# TH8_EEM_connector.net
KiCad netlist of a schematic drawn in Altium Designer
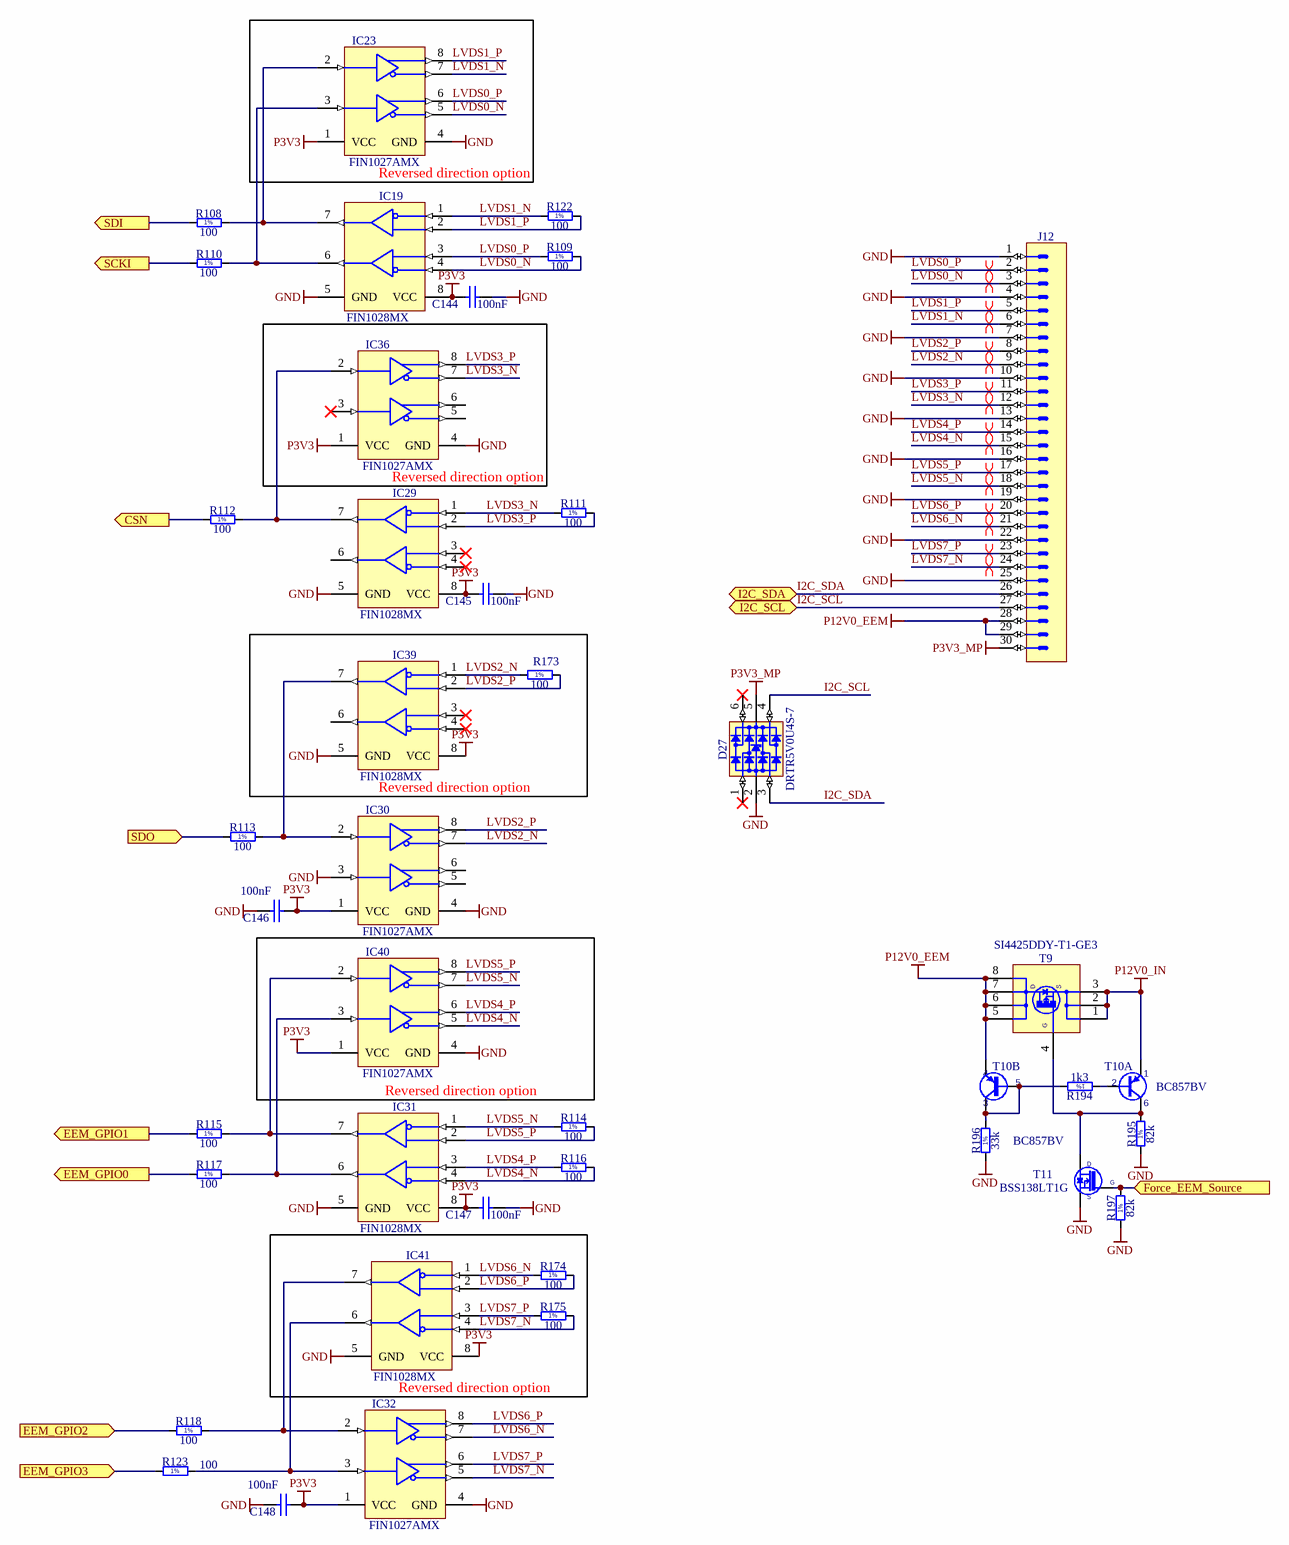
[diagram p0: TH8_EEM_connector.SchDoc]

(export (version "E")
  (design (tool "Eeschema 10.0.6"))
  (components
    (comp (ref "C144")
      (value "100nF")
      (footprint "CAPC1005X55N")
      (description "Non-polarised capacitor")
      (fields
        (field (name "PART NUMBER") "CC0402_100NF_16V_10%_X5R")
        (field (name "VOLTAGE") "16V")
        (field (name "AUTHOR") "CERN DEM JLC")
      )
      (libsource (lib "Capacitors") (part "Capacitor - non polarized"))
    )
    (comp (ref "C145")
      (value "100nF")
      (footprint "CAPC1005X55N")
      (description "Non-polarised capacitor")
      (fields
        (field (name "PART NUMBER") "CC0402_100NF_16V_10%_X5R")
        (field (name "VOLTAGE") "16V")
        (field (name "AUTHOR") "CERN DEM JLC")
      )
      (libsource (lib "Capacitors") (part "Capacitor - non polarized"))
    )
    (comp (ref "C146")
      (value "100nF")
      (footprint "CAPC1005X55N")
      (description "Non-polarised capacitor")
      (fields
        (field (name "PART NUMBER") "CC0402_100NF_16V_10%_X5R")
        (field (name "VOLTAGE") "16V")
        (field (name "AUTHOR") "CERN DEM JLC")
      )
      (libsource (lib "Capacitors") (part "Capacitor - non polarized"))
    )
    (comp (ref "C147")
      (value "100nF")
      (footprint "CAPC1005X55N")
      (description "Non-polarised capacitor")
      (fields
        (field (name "PART NUMBER") "CC0402_100NF_16V_10%_X5R")
        (field (name "VOLTAGE") "16V")
        (field (name "AUTHOR") "CERN DEM JLC")
      )
      (libsource (lib "Capacitors") (part "Capacitor - non polarized"))
    )
    (comp (ref "C148")
      (value "100nF")
      (footprint "CAPC1005X55N")
      (description "Non-polarised capacitor")
      (fields
        (field (name "PART NUMBER") "CC0402_100NF_16V_10%_X5R")
        (field (name "VOLTAGE") "16V")
        (field (name "AUTHOR") "CERN DEM JLC")
      )
      (libsource (lib "Capacitors") (part "Capacitor - non polarized"))
    )
    (comp (ref "D27")
      (value "DRTR5V0U4S-7")
      (footprint "SOT65P210X110-6N")
      (description "Integrated Quad Ultra-Low Capacitance ESD Protection")
      (fields (field (name "MANUFACTURER") "DIODES") (field (name "AUTHOR") "GK"))
      (libsource (lib "Diodes") (part "D_TVS_DRTR5V0U4S-7"))
    )
    (comp (ref "IC19")
      (value "FIN1028MX")
      (footprint "SOIC127P600X175-8N")
      (description "3.3V LVDS 2-Bit High-Speed Differential Reciever")
      (fields (field (name "MANUFACTURER") "ON Semiconductor") (field (name "AUTHOR") "GK"))
      (libsource (lib "LIBRARY_SCH") (part "IFC_FIN1028"))
    )
    (comp (ref "IC23")
      (value "FIN1027AMX")
      (footprint "SOIC127P600X175-8N")
      (description "3.3V LVDS, 2-Bit, High-Speed, Differential Driver")
      (fields (field (name "MANUFACTURER") "ON Semiconductor") (field (name "AUTHOR") "GK"))
      (libsource (lib "LIBRARY_SCH") (part "IFC_FIN1027A"))
    )
    (comp (ref "IC29")
      (value "FIN1028MX")
      (footprint "SOIC127P600X175-8N")
      (description "3.3V LVDS 2-Bit High-Speed Differential Reciever")
      (fields (field (name "MANUFACTURER") "ON Semiconductor") (field (name "AUTHOR") "GK"))
      (libsource (lib "LIBRARY_SCH") (part "IFC_FIN1028"))
    )
    (comp (ref "IC30")
      (value "FIN1027AMX")
      (footprint "SOIC127P600X175-8N")
      (description "3.3V LVDS, 2-Bit, High-Speed, Differential Driver")
      (fields (field (name "MANUFACTURER") "ON Semiconductor") (field (name "AUTHOR") "GK"))
      (libsource (lib "LIBRARY_SCH") (part "IFC_FIN1027A"))
    )
    (comp (ref "IC31")
      (value "FIN1028MX")
      (footprint "SOIC127P600X175-8N")
      (description "3.3V LVDS 2-Bit High-Speed Differential Reciever")
      (fields (field (name "MANUFACTURER") "ON Semiconductor") (field (name "AUTHOR") "GK"))
      (libsource (lib "LIBRARY_SCH") (part "IFC_FIN1028"))
    )
    (comp (ref "IC32")
      (value "FIN1027AMX")
      (footprint "SOIC127P600X175-8N")
      (description "3.3V LVDS, 2-Bit, High-Speed, Differential Driver")
      (fields (field (name "MANUFACTURER") "ON Semiconductor") (field (name "AUTHOR") "GK"))
      (libsource (lib "LIBRARY_SCH") (part "IFC_FIN1027A"))
    )
    (comp (ref "IC36")
      (value "FIN1027AMX")
      (footprint "SOIC127P600X175-8N")
      (description "3.3V LVDS, 2-Bit, High-Speed, Differential Driver")
      (fields (field (name "MANUFACTURER") "ON Semiconductor") (field (name "AUTHOR") "GK"))
      (libsource (lib "LIBRARY_SCH") (part "IFC_FIN1027A"))
    )
    (comp (ref "IC39")
      (value "FIN1028MX")
      (footprint "SOIC127P600X175-8N")
      (description "3.3V LVDS 2-Bit High-Speed Differential Reciever")
      (fields (field (name "MANUFACTURER") "ON Semiconductor") (field (name "AUTHOR") "GK"))
      (libsource (lib "LIBRARY_SCH") (part "IFC_FIN1028"))
    )
    (comp (ref "IC40")
      (value "FIN1027AMX")
      (footprint "SOIC127P600X175-8N")
      (description "3.3V LVDS, 2-Bit, High-Speed, Differential Driver")
      (fields (field (name "MANUFACTURER") "ON Semiconductor") (field (name "AUTHOR") "GK"))
      (libsource (lib "LIBRARY_SCH") (part "IFC_FIN1027A"))
    )
    (comp (ref "IC41")
      (value "FIN1028MX")
      (footprint "SOIC127P600X175-8N")
      (description "3.3V LVDS 2-Bit High-Speed Differential Reciever")
      (fields (field (name "MANUFACTURER") "ON Semiconductor") (field (name "AUTHOR") "GK"))
      (libsource (lib "LIBRARY_SCH") (part "IFC_FIN1028"))
    )
    (comp (ref "J12")
      (value "~")
      (footprint "3M_N2530-6002RB")
      (description "Connector 30 Male")
      (fields
        (field (name "PART NUMBER") "3M_N2530-6002RB")
        (field (name "MANUFACTURER") "3M")
        (field (name "AUTHOR") "CERN DEM JLC")
      )
      (libsource (lib "Connectors") (part "Connector 30 Male"))
    )
    (comp (ref "R108")
      (value "100")
      (footprint "RESC1005X40N")
      (description "Resistor - 1%")
      (fields
        (field (name "PART NUMBER") "R0402_100R_1%_0.0625W_100PPM")
        (field (name "POWER") "0.0625W")
        (field (name "AUTHOR") "CERN DEM JLC")
      )
      (libsource (lib "Resistors") (part "Resistor - 1%"))
    )
    (comp (ref "R109")
      (value "100")
      (footprint "RESC1005X40N")
      (description "Resistor - 1%")
      (fields
        (field (name "PART NUMBER") "R0402_100R_1%_0.0625W_100PPM")
        (field (name "POWER") "0.0625W")
        (field (name "AUTHOR") "CERN DEM JLC")
      )
      (libsource (lib "Resistors") (part "Resistor - 1%"))
    )
    (comp (ref "R110")
      (value "100")
      (footprint "RESC1005X40N")
      (description "Resistor - 1%")
      (fields
        (field (name "PART NUMBER") "R0402_100R_1%_0.0625W_100PPM")
        (field (name "POWER") "0.0625W")
        (field (name "AUTHOR") "CERN DEM JLC")
      )
      (libsource (lib "Resistors") (part "Resistor - 1%"))
    )
    (comp (ref "R111")
      (value "100")
      (footprint "RESC1005X40N")
      (description "Resistor - 1%")
      (fields
        (field (name "PART NUMBER") "R0402_100R_1%_0.0625W_100PPM")
        (field (name "POWER") "0.0625W")
        (field (name "AUTHOR") "CERN DEM JLC")
      )
      (libsource (lib "Resistors") (part "Resistor - 1%"))
    )
    (comp (ref "R112")
      (value "100")
      (footprint "RESC1005X40N")
      (description "Resistor - 1%")
      (fields
        (field (name "PART NUMBER") "R0402_100R_1%_0.0625W_100PPM")
        (field (name "POWER") "0.0625W")
        (field (name "AUTHOR") "CERN DEM JLC")
      )
      (libsource (lib "Resistors") (part "Resistor - 1%"))
    )
    (comp (ref "R113")
      (value "100")
      (footprint "RESC1005X40N")
      (description "Resistor - 1%")
      (fields
        (field (name "PART NUMBER") "R0402_100R_1%_0.0625W_100PPM")
        (field (name "POWER") "0.0625W")
        (field (name "AUTHOR") "CERN DEM JLC")
      )
      (libsource (lib "Resistors") (part "Resistor - 1%"))
    )
    (comp (ref "R114")
      (value "100")
      (footprint "RESC1005X40N")
      (description "Resistor - 1%")
      (fields
        (field (name "PART NUMBER") "R0402_100R_1%_0.0625W_100PPM")
        (field (name "POWER") "0.0625W")
        (field (name "AUTHOR") "CERN DEM JLC")
      )
      (libsource (lib "Resistors") (part "Resistor - 1%"))
    )
    (comp (ref "R115")
      (value "100")
      (footprint "RESC1005X40N")
      (description "Resistor - 1%")
      (fields
        (field (name "PART NUMBER") "R0402_100R_1%_0.0625W_100PPM")
        (field (name "POWER") "0.0625W")
        (field (name "AUTHOR") "CERN DEM JLC")
      )
      (libsource (lib "Resistors") (part "Resistor - 1%"))
    )
    (comp (ref "R116")
      (value "100")
      (footprint "RESC1005X40N")
      (description "Resistor - 1%")
      (fields
        (field (name "PART NUMBER") "R0402_100R_1%_0.0625W_100PPM")
        (field (name "POWER") "0.0625W")
        (field (name "AUTHOR") "CERN DEM JLC")
      )
      (libsource (lib "Resistors") (part "Resistor - 1%"))
    )
    (comp (ref "R117")
      (value "100")
      (footprint "RESC1005X40N")
      (description "Resistor - 1%")
      (fields
        (field (name "PART NUMBER") "R0402_100R_1%_0.0625W_100PPM")
        (field (name "POWER") "0.0625W")
        (field (name "AUTHOR") "CERN DEM JLC")
      )
      (libsource (lib "Resistors") (part "Resistor - 1%"))
    )
    (comp (ref "R118")
      (value "100")
      (footprint "RESC1005X40N")
      (description "Resistor - 1%")
      (fields
        (field (name "PART NUMBER") "R0402_100R_1%_0.0625W_100PPM")
        (field (name "POWER") "0.0625W")
        (field (name "AUTHOR") "CERN DEM JLC")
      )
      (libsource (lib "Resistors") (part "Resistor - 1%"))
    )
    (comp (ref "R122")
      (value "100")
      (footprint "RESC1005X40N")
      (description "Resistor - 1%")
      (fields
        (field (name "PART NUMBER") "R0402_100R_1%_0.0625W_100PPM")
        (field (name "POWER") "0.0625W")
        (field (name "AUTHOR") "CERN DEM JLC")
      )
      (libsource (lib "Resistors") (part "Resistor - 1%"))
    )
    (comp (ref "R123")
      (value "100")
      (footprint "RESC1005X40N")
      (description "Resistor - 1%")
      (fields
        (field (name "PART NUMBER") "R0402_100R_1%_0.0625W_100PPM")
        (field (name "POWER") "0.0625W")
        (field (name "AUTHOR") "CERN DEM JLC")
      )
      (libsource (lib "Resistors") (part "Resistor - 1%"))
    )
    (comp (ref "R173")
      (value "100")
      (footprint "RESC1005X40N")
      (description "Resistor - 1%")
      (fields
        (field (name "PART NUMBER") "R0402_100R_1%_0.0625W_100PPM")
        (field (name "POWER") "0.0625W")
        (field (name "AUTHOR") "CERN DEM JLC")
      )
      (libsource (lib "Resistors") (part "Resistor - 1%"))
    )
    (comp (ref "R174")
      (value "100")
      (footprint "RESC1005X40N")
      (description "Resistor - 1%")
      (fields
        (field (name "PART NUMBER") "R0402_100R_1%_0.0625W_100PPM")
        (field (name "POWER") "0.0625W")
        (field (name "AUTHOR") "CERN DEM JLC")
      )
      (libsource (lib "Resistors") (part "Resistor - 1%"))
    )
    (comp (ref "R175")
      (value "100")
      (footprint "RESC1005X40N")
      (description "Resistor - 1%")
      (fields
        (field (name "PART NUMBER") "R0402_100R_1%_0.0625W_100PPM")
        (field (name "POWER") "0.0625W")
        (field (name "AUTHOR") "CERN DEM JLC")
      )
      (libsource (lib "Resistors") (part "Resistor - 1%"))
    )
    (comp (ref "R194")
      (value "1k3")
      (footprint "RESC1608X55N")
      (description "Resistor - 1%")
      (fields
        (field (name "PART NUMBER") "R0603_1K3_1%_0.1W_100PPM")
        (field (name "POWER") "0.1W")
        (field (name "AUTHOR") "CERN DEM JLC")
      )
      (libsource (lib "Resistors") (part "Resistor - 1%"))
    )
    (comp (ref "R195")
      (value "82k")
      (footprint "RESC1608X55N")
      (description "Resistor - 1%")
      (fields
        (field (name "PART NUMBER") "R0603_82K_1%_0.1W_100PPM")
        (field (name "POWER") "0.1W")
        (field (name "AUTHOR") "CERN DEM JLC")
      )
      (libsource (lib "Resistors") (part "Resistor - 1%"))
    )
    (comp (ref "R196")
      (value "33k")
      (footprint "RESC1005X40N")
      (description "Resistor - 1%")
      (fields
        (field (name "PART NUMBER") "R0402_33K_1%_0.0625W_100PPM")
        (field (name "POWER") "0.0625W")
        (field (name "AUTHOR") "CERN DEM JLC")
      )
      (libsource (lib "Resistors") (part "Resistor - 1%"))
    )
    (comp (ref "R197")
      (value "82k")
      (footprint "RESC1608X55N")
      (description "Resistor - 1%")
      (fields
        (field (name "PART NUMBER") "R0603_82K_1%_0.1W_100PPM")
        (field (name "POWER") "0.1W")
        (field (name "AUTHOR") "CERN DEM JLC")
      )
      (libsource (lib "Resistors") (part "Resistor - 1%"))
    )
    (comp (ref "T9")
      (value "SI4425DDY-T1-GE3")
      (footprint "SOIC127P600X175-8N")
      (description "-30V -19.7A P-Channel MOSFET")
      (fields (field (name "MANUFACTURER") "VISHAY SILICONIX") (field (name "AUTHOR") "CERN DEM MR"))
      (libsource (lib "ICs And Semiconductors") (part "SI4425DDY"))
    )
    (comp (ref "T10")
      (value "BC857BV")
      (footprint "SOTFL50P160X60-6N")
      (description "45V, 100mA PNP General Purpose Double Transistor")
      (fields (field (name "MANUFACTURER") "NXP SEMICONDUCTORS") (field (name "AUTHOR") "CERN DEM JLC"))
      (libsource (lib "ICs And Semiconductors") (part "BC857BV"))
    )
    (comp (ref "T11")
      (value "BSS138LT1G")
      (footprint "SOT95P240X110-3N")
      (description "N-CHANNEL MOSFET WITH DIODE")
      (fields (field (name "MANUFACTURER") "ON SEMICONDUCTOR") (field (name "AUTHOR") "CERN DEM JLC"))
      (libsource (lib "ICs And Semiconductors") (part "N-MOSFET-D 1G 2S 3D"))
    )
  )
  (nets
    (net (code "1") (name "/CSN") (class "Default")
      (node (ref "R112") (pin "1") (pinfunction "1_1") (pintype "passive"))
    )
    (net (code "2") (name "/EEM_GPIO0") (class "Default")
      (node (ref "R117") (pin "1") (pinfunction "1_1") (pintype "passive"))
    )
    (net (code "3") (name "/EEM_GPIO1") (class "Default")
      (node (ref "R115") (pin "1") (pinfunction "1_1") (pintype "passive"))
    )
    (net (code "4") (name "/EEM_GPIO2") (class "Default")
      (node (ref "R118") (pin "1") (pinfunction "1_1") (pintype "passive"))
    )
    (net (code "5") (name "/EEM_GPIO3") (class "Default")
      (node (ref "R123") (pin "1") (pinfunction "1_1") (pintype "passive"))
    )
    (net (code "6") (name "/Force_EEM_Source") (class "Default")
      (node (ref "R197") (pin "2") (pinfunction "2_2") (pintype "passive"))
      (node (ref "T11") (pin "1") (pinfunction "G_1") (pintype "passive"))
    )
    (net (code "7") (name "/I2C_SCL") (class "Default")
      (node (ref "D27") (pin "4") (pinfunction "I/O3_4") (pintype "bidirectional"))
      (node (ref "J12") (pin "27") (pinfunction "27_27") (pintype "bidirectional"))
    )
    (net (code "8") (name "/I2C_SDA") (class "Default")
      (node (ref "D27") (pin "3") (pinfunction "I/O2_3") (pintype "bidirectional"))
      (node (ref "J12") (pin "26") (pinfunction "26_26") (pintype "bidirectional"))
    )
    (net (code "9") (name "/LVDS0_N") (class "Default")
      (node (ref "IC19") (pin "4") (pinfunction "RIN2-_4") (pintype "input"))
      (node (ref "IC23") (pin "5") (pinfunction "DOUT-_5") (pintype "output"))
      (node (ref "J12") (pin "3") (pinfunction "3_3") (pintype "bidirectional"))
      (node (ref "R109") (pin "2") (pinfunction "2_2") (pintype "passive"))
    )
    (net (code "10") (name "/LVDS0_P") (class "Default")
      (node (ref "IC19") (pin "3") (pinfunction "RIN2+_3") (pintype "input"))
      (node (ref "IC23") (pin "6") (pinfunction "DOUT+_6") (pintype "output"))
      (node (ref "J12") (pin "2") (pinfunction "2_2") (pintype "bidirectional"))
      (node (ref "R109") (pin "1") (pinfunction "1_1") (pintype "passive"))
    )
    (net (code "11") (name "/LVDS1_N") (class "Default")
      (node (ref "IC19") (pin "1") (pinfunction "RIN1-_1") (pintype "input"))
      (node (ref "IC23") (pin "7") (pinfunction "DOUT-_7") (pintype "output"))
      (node (ref "J12") (pin "6") (pinfunction "6_6") (pintype "bidirectional"))
      (node (ref "R122") (pin "1") (pinfunction "1_1") (pintype "passive"))
    )
    (net (code "12") (name "/LVDS1_P") (class "Default")
      (node (ref "IC19") (pin "2") (pinfunction "RIN1+_2") (pintype "input"))
      (node (ref "IC23") (pin "8") (pinfunction "DOUT+_8") (pintype "output"))
      (node (ref "J12") (pin "5") (pinfunction "5_5") (pintype "bidirectional"))
      (node (ref "R122") (pin "2") (pinfunction "2_2") (pintype "passive"))
    )
    (net (code "13") (name "/LVDS2_N") (class "Default")
      (node (ref "IC30") (pin "7") (pinfunction "DOUT-_7") (pintype "output"))
      (node (ref "IC39") (pin "1") (pinfunction "RIN1-_1") (pintype "input"))
      (node (ref "J12") (pin "9") (pinfunction "9_9") (pintype "bidirectional"))
      (node (ref "R173") (pin "1") (pinfunction "1_1") (pintype "passive"))
    )
    (net (code "14") (name "/LVDS2_P") (class "Default")
      (node (ref "IC30") (pin "8") (pinfunction "DOUT+_8") (pintype "output"))
      (node (ref "IC39") (pin "2") (pinfunction "RIN1+_2") (pintype "input"))
      (node (ref "J12") (pin "8") (pinfunction "8_8") (pintype "bidirectional"))
      (node (ref "R173") (pin "2") (pinfunction "2_2") (pintype "passive"))
    )
    (net (code "15") (name "/LVDS3_N") (class "Default")
      (node (ref "IC29") (pin "1") (pinfunction "RIN1-_1") (pintype "input"))
      (node (ref "IC36") (pin "7") (pinfunction "DOUT-_7") (pintype "output"))
      (node (ref "J12") (pin "12") (pinfunction "12_12") (pintype "bidirectional"))
      (node (ref "R111") (pin "1") (pinfunction "1_1") (pintype "passive"))
    )
    (net (code "16") (name "/LVDS3_P") (class "Default")
      (node (ref "IC29") (pin "2") (pinfunction "RIN1+_2") (pintype "input"))
      (node (ref "IC36") (pin "8") (pinfunction "DOUT+_8") (pintype "output"))
      (node (ref "J12") (pin "11") (pinfunction "11_11") (pintype "bidirectional"))
      (node (ref "R111") (pin "2") (pinfunction "2_2") (pintype "passive"))
    )
    (net (code "17") (name "/LVDS4_N") (class "Default")
      (node (ref "IC31") (pin "4") (pinfunction "RIN2-_4") (pintype "input"))
      (node (ref "IC40") (pin "5") (pinfunction "DOUT-_5") (pintype "output"))
      (node (ref "J12") (pin "15") (pinfunction "15_15") (pintype "bidirectional"))
      (node (ref "R116") (pin "2") (pinfunction "2_2") (pintype "passive"))
    )
    (net (code "18") (name "/LVDS4_P") (class "Default")
      (node (ref "IC31") (pin "3") (pinfunction "RIN2+_3") (pintype "input"))
      (node (ref "IC40") (pin "6") (pinfunction "DOUT+_6") (pintype "output"))
      (node (ref "J12") (pin "14") (pinfunction "14_14") (pintype "bidirectional"))
      (node (ref "R116") (pin "1") (pinfunction "1_1") (pintype "passive"))
    )
    (net (code "19") (name "/LVDS5_N") (class "Default")
      (node (ref "IC31") (pin "1") (pinfunction "RIN1-_1") (pintype "input"))
      (node (ref "IC40") (pin "7") (pinfunction "DOUT-_7") (pintype "output"))
      (node (ref "J12") (pin "18") (pinfunction "18_18") (pintype "bidirectional"))
      (node (ref "R114") (pin "1") (pinfunction "1_1") (pintype "passive"))
    )
    (net (code "20") (name "/LVDS5_P") (class "Default")
      (node (ref "IC31") (pin "2") (pinfunction "RIN1+_2") (pintype "input"))
      (node (ref "IC40") (pin "8") (pinfunction "DOUT+_8") (pintype "output"))
      (node (ref "J12") (pin "17") (pinfunction "17_17") (pintype "bidirectional"))
      (node (ref "R114") (pin "2") (pinfunction "2_2") (pintype "passive"))
    )
    (net (code "21") (name "/LVDS6_N") (class "Default")
      (node (ref "IC32") (pin "7") (pinfunction "DOUT-_7") (pintype "output"))
      (node (ref "IC41") (pin "1") (pinfunction "RIN1-_1") (pintype "input"))
      (node (ref "J12") (pin "21") (pinfunction "21_21") (pintype "bidirectional"))
      (node (ref "R174") (pin "1") (pinfunction "1_1") (pintype "passive"))
    )
    (net (code "22") (name "/LVDS6_P") (class "Default")
      (node (ref "IC32") (pin "8") (pinfunction "DOUT+_8") (pintype "output"))
      (node (ref "IC41") (pin "2") (pinfunction "RIN1+_2") (pintype "input"))
      (node (ref "J12") (pin "20") (pinfunction "20_20") (pintype "bidirectional"))
      (node (ref "R174") (pin "2") (pinfunction "2_2") (pintype "passive"))
    )
    (net (code "23") (name "/LVDS7_N") (class "Default")
      (node (ref "IC32") (pin "5") (pinfunction "DOUT-_5") (pintype "output"))
      (node (ref "IC41") (pin "4") (pinfunction "RIN2-_4") (pintype "input"))
      (node (ref "J12") (pin "24") (pinfunction "24_24") (pintype "bidirectional"))
      (node (ref "R175") (pin "2") (pinfunction "2_2") (pintype "passive"))
    )
    (net (code "24") (name "/LVDS7_P") (class "Default")
      (node (ref "IC32") (pin "6") (pinfunction "DOUT+_6") (pintype "output"))
      (node (ref "IC41") (pin "3") (pinfunction "RIN2+_3") (pintype "input"))
      (node (ref "J12") (pin "23") (pinfunction "23_23") (pintype "bidirectional"))
      (node (ref "R175") (pin "1") (pinfunction "1_1") (pintype "passive"))
    )
    (net (code "25") (name "/SCKI") (class "Default")
      (node (ref "R110") (pin "1") (pinfunction "1_1") (pintype "passive"))
    )
    (net (code "26") (name "/SDI") (class "Default")
      (node (ref "R108") (pin "1") (pinfunction "1_1") (pintype "passive"))
    )
    (net (code "27") (name "/SDO") (class "Default")
      (node (ref "R113") (pin "1") (pinfunction "1_1") (pintype "passive"))
    )
    (net (code "28") (name "GND") (class "Default")
      (node (ref "C144") (pin "1") (pinfunction "1_1") (pintype "passive"))
      (node (ref "C145") (pin "1") (pinfunction "1_1") (pintype "passive"))
      (node (ref "C146") (pin "1") (pinfunction "1_1") (pintype "passive"))
      (node (ref "C147") (pin "1") (pinfunction "1_1") (pintype "passive"))
      (node (ref "C148") (pin "1") (pinfunction "1_1") (pintype "passive"))
      (node (ref "D27") (pin "2") (pinfunction "GND_2") (pintype "power_in"))
      (node (ref "IC19") (pin "5") (pinfunction "GND_5") (pintype "power_in"))
      (node (ref "IC23") (pin "4") (pinfunction "GND_4") (pintype "power_in"))
      (node (ref "IC29") (pin "5") (pinfunction "GND_5") (pintype "power_in"))
      (node (ref "IC30") (pin "3") (pinfunction "DIN2RIN-_3") (pintype "input"))
      (node (ref "IC30") (pin "4") (pinfunction "GND_4") (pintype "power_in"))
      (node (ref "IC31") (pin "5") (pinfunction "GND_5") (pintype "power_in"))
      (node (ref "IC32") (pin "4") (pinfunction "GND_4") (pintype "power_in"))
      (node (ref "IC36") (pin "4") (pinfunction "GND_4") (pintype "power_in"))
      (node (ref "IC39") (pin "5") (pinfunction "GND_5") (pintype "power_in"))
      (node (ref "IC40") (pin "4") (pinfunction "GND_4") (pintype "power_in"))
      (node (ref "IC41") (pin "5") (pinfunction "GND_5") (pintype "power_in"))
      (node (ref "J12") (pin "1") (pinfunction "1_1") (pintype "bidirectional"))
      (node (ref "J12") (pin "10") (pinfunction "10_10") (pintype "bidirectional"))
      (node (ref "J12") (pin "13") (pinfunction "13_13") (pintype "bidirectional"))
      (node (ref "J12") (pin "16") (pinfunction "16_16") (pintype "bidirectional"))
      (node (ref "J12") (pin "19") (pinfunction "19_19") (pintype "bidirectional"))
      (node (ref "J12") (pin "22") (pinfunction "22_22") (pintype "bidirectional"))
      (node (ref "J12") (pin "25") (pinfunction "25_25") (pintype "bidirectional"))
      (node (ref "J12") (pin "4") (pinfunction "4_4") (pintype "bidirectional"))
      (node (ref "J12") (pin "7") (pinfunction "7_7") (pintype "bidirectional"))
      (node (ref "R195") (pin "1") (pinfunction "1_1") (pintype "passive"))
      (node (ref "R196") (pin "1") (pinfunction "1_1") (pintype "passive"))
      (node (ref "R197") (pin "1") (pinfunction "1_1") (pintype "passive"))
      (node (ref "T11") (pin "2") (pinfunction "S_2") (pintype "passive"))
    )
    (net (code "29") (name "Net-(IC19-ROUT1)") (class "Default")
      (node (ref "IC19") (pin "7") (pinfunction "ROUT1_7") (pintype "output"))
      (node (ref "IC23") (pin "2") (pinfunction "DIN1_2") (pintype "input"))
      (node (ref "R108") (pin "2") (pinfunction "2_2") (pintype "passive"))
    )
    (net (code "30") (name "Net-(IC19-ROUT2)") (class "Default")
      (node (ref "IC19") (pin "6") (pinfunction "ROUT2_6") (pintype "output"))
      (node (ref "IC23") (pin "3") (pinfunction "DIN2RIN-_3") (pintype "input"))
      (node (ref "R110") (pin "2") (pinfunction "2_2") (pintype "passive"))
    )
    (net (code "31") (name "Net-(IC29-ROUT1)") (class "Default")
      (node (ref "IC29") (pin "7") (pinfunction "ROUT1_7") (pintype "output"))
      (node (ref "IC36") (pin "2") (pinfunction "DIN1_2") (pintype "input"))
      (node (ref "R112") (pin "2") (pinfunction "2_2") (pintype "passive"))
    )
    (net (code "32") (name "Net-(IC30-DIN1)") (class "Default")
      (node (ref "IC30") (pin "2") (pinfunction "DIN1_2") (pintype "input"))
      (node (ref "IC39") (pin "7") (pinfunction "ROUT1_7") (pintype "output"))
      (node (ref "R113") (pin "2") (pinfunction "2_2") (pintype "passive"))
    )
    (net (code "33") (name "Net-(IC31-ROUT1)") (class "Default")
      (node (ref "IC31") (pin "7") (pinfunction "ROUT1_7") (pintype "output"))
      (node (ref "IC40") (pin "2") (pinfunction "DIN1_2") (pintype "input"))
      (node (ref "R115") (pin "2") (pinfunction "2_2") (pintype "passive"))
    )
    (net (code "34") (name "Net-(IC31-ROUT2)") (class "Default")
      (node (ref "IC31") (pin "6") (pinfunction "ROUT2_6") (pintype "output"))
      (node (ref "IC40") (pin "3") (pinfunction "DIN2RIN-_3") (pintype "input"))
      (node (ref "R117") (pin "2") (pinfunction "2_2") (pintype "passive"))
    )
    (net (code "35") (name "Net-(IC32-DIN1)") (class "Default")
      (node (ref "IC32") (pin "2") (pinfunction "DIN1_2") (pintype "input"))
      (node (ref "IC41") (pin "7") (pinfunction "ROUT1_7") (pintype "output"))
      (node (ref "R118") (pin "2") (pinfunction "2_2") (pintype "passive"))
    )
    (net (code "36") (name "Net-(IC32-DIN2RIN-)") (class "Default")
      (node (ref "IC32") (pin "3") (pinfunction "DIN2RIN-_3") (pintype "input"))
      (node (ref "IC41") (pin "6") (pinfunction "ROUT2_6") (pintype "output"))
      (node (ref "R123") (pin "2") (pinfunction "2_2") (pintype "passive"))
    )
    (net (code "37") (name "Net-(T10A-B)") (class "Default")
      (node (ref "R194") (pin "1") (pinfunction "1_1") (pintype "passive"))
      (node (ref "T10") (pin "2") (pinfunction "B_2") (pintype "passive"))
    )
    (net (code "38") (name "Net-(T10A-C)") (class "Default")
      (node (ref "R195") (pin "2") (pinfunction "2_2") (pintype "passive"))
      (node (ref "T10") (pin "6") (pinfunction "C_6") (pintype "passive"))
      (node (ref "T11") (pin "3") (pinfunction "D_3") (pintype "passive"))
      (node (ref "T9") (pin "4") (pinfunction "S_4") (pintype "passive"))
    )
    (net (code "39") (name "Net-(T10B-B)") (class "Default")
      (node (ref "R194") (pin "2") (pinfunction "2_2") (pintype "passive"))
      (node (ref "R196") (pin "2") (pinfunction "2_2") (pintype "passive"))
      (node (ref "T10") (pin "3") (pinfunction "C_3") (pintype "passive"))
      (node (ref "T10") (pin "5") (pinfunction "B_5") (pintype "passive"))
    )
    (net (code "40") (name "P3V3") (class "Default")
      (node (ref "C144") (pin "2") (pinfunction "2_2") (pintype "passive"))
      (node (ref "C145") (pin "2") (pinfunction "2_2") (pintype "passive"))
      (node (ref "C146") (pin "2") (pinfunction "2_2") (pintype "passive"))
      (node (ref "C147") (pin "2") (pinfunction "2_2") (pintype "passive"))
      (node (ref "C148") (pin "2") (pinfunction "2_2") (pintype "passive"))
      (node (ref "IC19") (pin "8") (pinfunction "VCC_8") (pintype "power_in"))
      (node (ref "IC23") (pin "1") (pinfunction "VCC_1") (pintype "power_in"))
      (node (ref "IC29") (pin "8") (pinfunction "VCC_8") (pintype "power_in"))
      (node (ref "IC30") (pin "1") (pinfunction "VCC_1") (pintype "power_in"))
      (node (ref "IC31") (pin "8") (pinfunction "VCC_8") (pintype "power_in"))
      (node (ref "IC32") (pin "1") (pinfunction "VCC_1") (pintype "power_in"))
      (node (ref "IC36") (pin "1") (pinfunction "VCC_1") (pintype "power_in"))
      (node (ref "IC39") (pin "8") (pinfunction "VCC_8") (pintype "power_in"))
      (node (ref "IC40") (pin "1") (pinfunction "VCC_1") (pintype "power_in"))
      (node (ref "IC41") (pin "8") (pinfunction "VCC_8") (pintype "power_in"))
    )
    (net (code "41") (name "P3V3_MP") (class "Default")
      (node (ref "D27") (pin "5") (pinfunction "VBUS_5") (pintype "power_in"))
      (node (ref "J12") (pin "30") (pinfunction "30_30") (pintype "bidirectional"))
    )
    (net (code "42") (name "P12V0_EEM") (class "Default")
      (node (ref "J12") (pin "28") (pinfunction "28_28") (pintype "bidirectional"))
      (node (ref "J12") (pin "29") (pinfunction "29_29") (pintype "bidirectional"))
      (node (ref "T10") (pin "4") (pinfunction "E_4") (pintype "passive"))
      (node (ref "T9") (pin "5") (pinfunction "D_5") (pintype "passive"))
      (node (ref "T9") (pin "6") (pinfunction "D_6") (pintype "passive"))
      (node (ref "T9") (pin "7") (pinfunction "D_7") (pintype "passive"))
      (node (ref "T9") (pin "8") (pinfunction "D_8") (pintype "passive"))
    )
    (net (code "43") (name "P12V0_IN") (class "Default")
      (node (ref "T10") (pin "1") (pinfunction "E_1") (pintype "passive"))
      (node (ref "T9") (pin "1") (pinfunction "S_1") (pintype "passive"))
      (node (ref "T9") (pin "2") (pinfunction "S_2") (pintype "passive"))
      (node (ref "T9") (pin "3") (pinfunction "S_3") (pintype "passive"))
    )
    (net (code "44") (name "unconnected-(D27-I{slash}O1-Pad1)") (class "Default")
      (node (ref "D27") (pin "1") (pinfunction "I/O1_1") (pintype "bidirectional+no_connect"))
    )
    (net (code "45") (name "unconnected-(D27-I{slash}O4-Pad6)") (class "Default")
      (node (ref "D27") (pin "6") (pinfunction "I/O4_6") (pintype "bidirectional+no_connect"))
    )
    (net (code "46") (name "unconnected-(IC29-RIN2+-Pad3)") (class "Default")
      (node (ref "IC29") (pin "3") (pinfunction "RIN2+_3") (pintype "input+no_connect"))
    )
    (net (code "47") (name "unconnected-(IC29-RIN2--Pad4)") (class "Default")
      (node (ref "IC29") (pin "4") (pinfunction "RIN2-_4") (pintype "input+no_connect"))
    )
    (net (code "48") (name "unconnected-(IC29-ROUT2-Pad6)") (class "Default")
      (node (ref "IC29") (pin "6") (pinfunction "ROUT2_6") (pintype "output"))
    )
    (net (code "49") (name "unconnected-(IC30-DOUT+-Pad6)") (class "Default")
      (node (ref "IC30") (pin "6") (pinfunction "DOUT+_6") (pintype "output"))
    )
    (net (code "50") (name "unconnected-(IC30-DOUT--Pad5)") (class "Default")
      (node (ref "IC30") (pin "5") (pinfunction "DOUT-_5") (pintype "output"))
    )
    (net (code "51") (name "unconnected-(IC36-DIN2RIN--Pad3)") (class "Default")
      (node (ref "IC36") (pin "3") (pinfunction "DIN2RIN-_3") (pintype "input+no_connect"))
    )
    (net (code "52") (name "unconnected-(IC36-DOUT+-Pad6)") (class "Default")
      (node (ref "IC36") (pin "6") (pinfunction "DOUT+_6") (pintype "output"))
    )
    (net (code "53") (name "unconnected-(IC36-DOUT--Pad5)") (class "Default")
      (node (ref "IC36") (pin "5") (pinfunction "DOUT-_5") (pintype "output"))
    )
    (net (code "54") (name "unconnected-(IC39-RIN2+-Pad3)") (class "Default")
      (node (ref "IC39") (pin "3") (pinfunction "RIN2+_3") (pintype "input+no_connect"))
    )
    (net (code "55") (name "unconnected-(IC39-RIN2--Pad4)") (class "Default")
      (node (ref "IC39") (pin "4") (pinfunction "RIN2-_4") (pintype "input+no_connect"))
    )
    (net (code "56") (name "unconnected-(IC39-ROUT2-Pad6)") (class "Default")
      (node (ref "IC39") (pin "6") (pinfunction "ROUT2_6") (pintype "output"))
    )
  )
)
